# Morpheus_bottom.net
KiCad netlist of a schematic drawn in Altium Designer
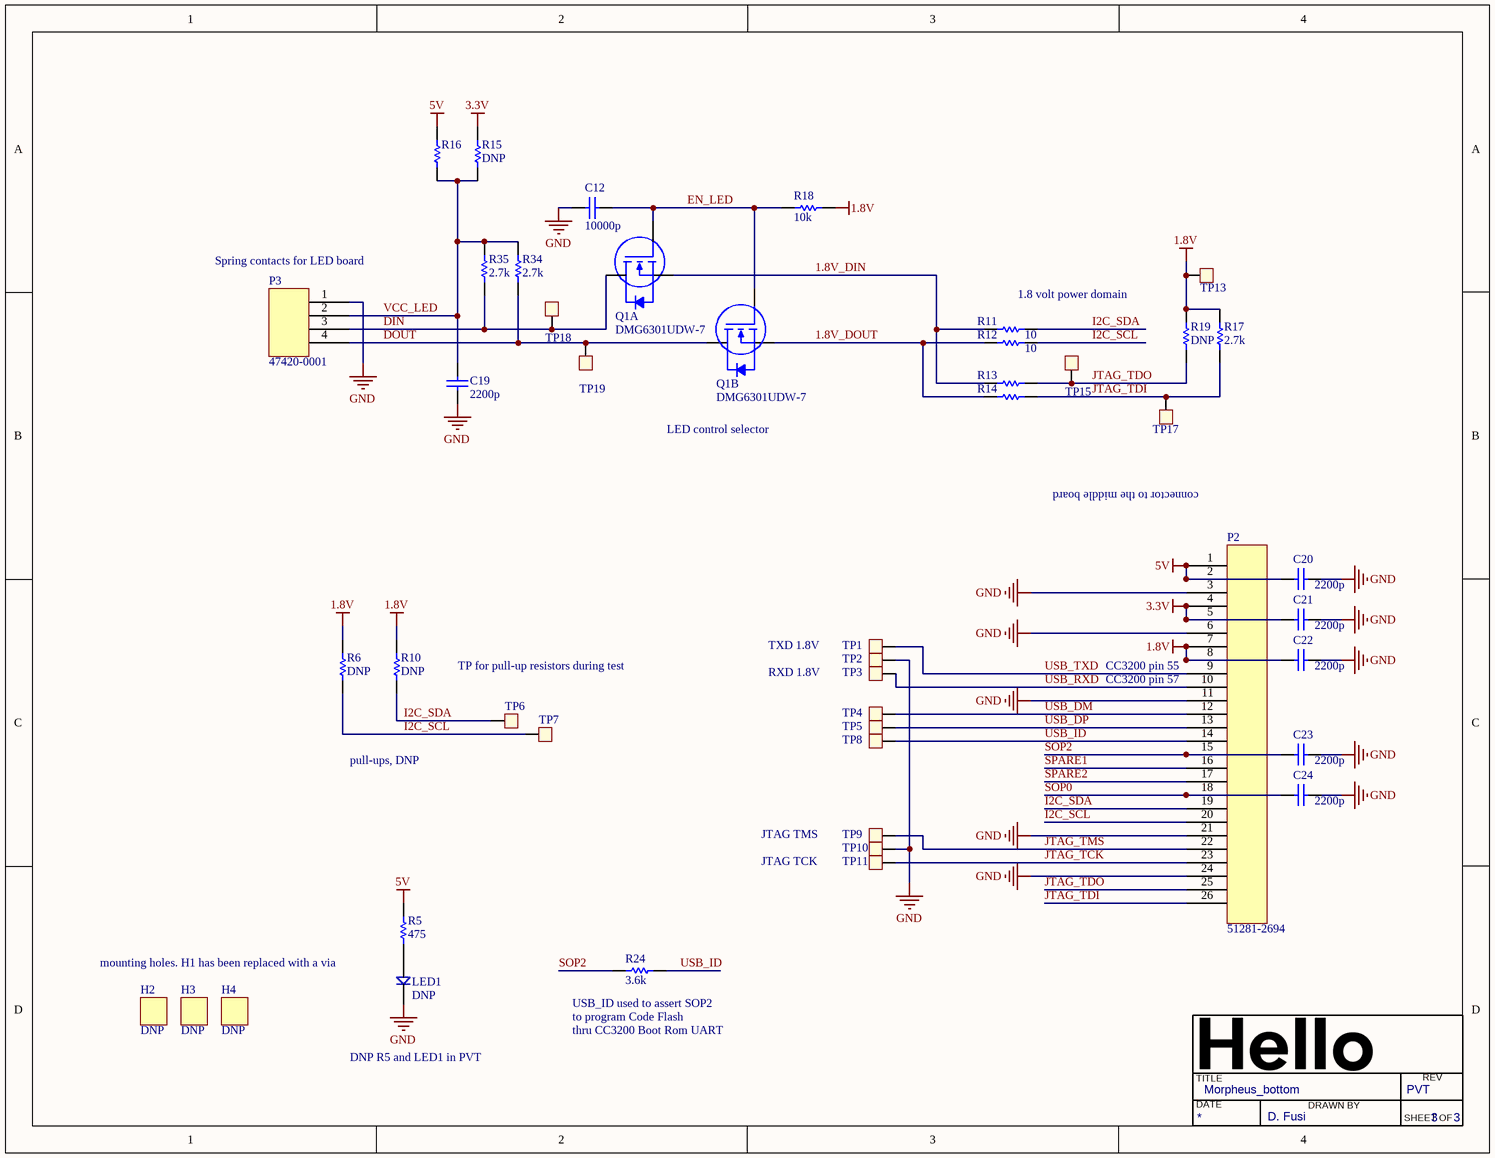
[diagram p0: Morpheus_bottom.SchDoc]

(export (version "E")
  (design (tool "Eeschema 10.0.6"))
  (components
    (comp (ref "C12")
      (value "10000p")
      (footprint "CAP0603_SENSE_DVT")
      (description "CAP CER 10000PF 50V 10% X7R 0603")
      (fields (field (name "TOLERANCE") "10%") (field (name "VOLTAGE") "50"))
      (libsource (lib "Morpheus_pill") (part "C_10000p_10_50_X7R_0603"))
    )
    (comp (ref "C19")
      (value "2200p")
      (footprint "CAP0402_SENSE_DVT")
      (description "CAP CER 2200PF 16V 10% X7R 0402")
      (fields (field (name "TOLERANCE") "10 %") (field (name "VOLTAGE") "16V"))
      (libsource (lib "Morpheus_pill") (part "C_2200p_5_16_STD_0402"))
    )
    (comp (ref "C20")
      (value "2200p")
      (footprint "CAP0402_SENSE_DVT")
      (description "CAP CER 2200PF 16V 10% X7R 0402")
      (fields (field (name "TOLERANCE") "10 %") (field (name "VOLTAGE") "16V"))
      (libsource (lib "Morpheus_pill") (part "C_2200p_5_16_STD_0402"))
    )
    (comp (ref "C21")
      (value "2200p")
      (footprint "CAP0402_SENSE_DVT")
      (description "CAP CER 2200PF 16V 10% X7R 0402")
      (fields (field (name "TOLERANCE") "10 %") (field (name "VOLTAGE") "16V"))
      (libsource (lib "Morpheus_pill") (part "C_2200p_5_16_STD_0402"))
    )
    (comp (ref "C22")
      (value "2200p")
      (footprint "CAP0402_SENSE_DVT")
      (description "CAP CER 2200PF 16V 10% X7R 0402")
      (fields (field (name "TOLERANCE") "10 %") (field (name "VOLTAGE") "16V"))
      (libsource (lib "Morpheus_pill") (part "C_2200p_5_16_STD_0402"))
    )
    (comp (ref "C23")
      (value "2200p")
      (footprint "CAP0402_SENSE_DVT")
      (description "CAP CER 2200PF 16V 10% X7R 0402")
      (fields (field (name "TOLERANCE") "10 %") (field (name "VOLTAGE") "16V"))
      (libsource (lib "Morpheus_pill") (part "C_2200p_5_16_STD_0402"))
    )
    (comp (ref "C24")
      (value "2200p")
      (footprint "CAP0402_SENSE_DVT")
      (description "CAP CER 2200PF 16V 10% X7R 0402")
      (fields (field (name "TOLERANCE") "10 %") (field (name "VOLTAGE") "16V"))
      (libsource (lib "Morpheus_pill") (part "C_2200p_5_16_STD_0402"))
    )
    (comp (ref "H2")
      (value "DNP")
      (footprint "HOLE_ROUND_1.8mm")
      (description "general purpose hole")
      (libsource (lib "Morpheus_pill") (part "Hole"))
    )
    (comp (ref "H3")
      (value "DNP")
      (footprint "HOLE_ROUND_1.8mm")
      (description "general purpose hole")
      (libsource (lib "Morpheus_pill") (part "Hole"))
    )
    (comp (ref "H4")
      (value "DNP")
      (footprint "HOLE_ROUND_1.8mm")
      (description "general purpose hole")
      (libsource (lib "Morpheus_pill") (part "Hole"))
    )
    (comp (ref "LED1")
      (value "DNP")
      (footprint "LED_Kingbright")
      (description "Kingbright Green SMT LED")
      (libsource (lib "Morpheus_pill") (part "APT2012SGC"))
    )
    (comp (ref "P2")
      (value "51281-2694")
      (footprint "molex_51281-2694_reverse")
      (description "Molex 26-pin 0.5mm pitch connector")
      (libsource (lib "Morpheus_pill") (part "51281-011"))
    )
    (comp (ref "P3")
      (value "47420-0001")
      (footprint "molex_47420-0001")
      (description "Molex 4-pin spring connector 1.8 mm working height")
      (libsource (lib "Morpheus_pill") (part "molex_47420-0001"))
    )
    (comp (ref "Q1")
      (value "DMG6301UDW-7")
      (footprint "SC-70-6")
      (description "MOSFET 2N-CH 25V 240MA SOT363")
      (libsource (lib "") (part "DMG6301UDW-7_1"))
    )
    (comp (ref "R5")
      (value "475")
      (footprint "RES0402_SENSE_DVT")
      (description "RES SMD 475 OHM 1% 1/16W 0402")
      (fields (field (name "TOLERANCE") "1 %") (field (name "POWER") "0.1 W"))
      (libsource (lib "Morpheus_pill") (part "R_475_1_0.1_0402"))
    )
    (comp (ref "R6")
      (value "DNP")
      (footprint "RES0603_SENSE_DVT")
      (description "Chip Resistor")
      (fields (field (name "TOLERANCE") "1 %") (field (name "POWER") "0.1 W"))
      (libsource (lib "Morpheus_pill") (part "R_2.7k_1_0.1_0603"))
    )
    (comp (ref "R10")
      (value "DNP")
      (footprint "RES0603_SENSE_DVT")
      (description "Chip Resistor")
      (fields (field (name "TOLERANCE") "1 %") (field (name "POWER") "0.1 W"))
      (libsource (lib "Morpheus_pill") (part "R_2.7k_1_0.1_0603"))
    )
    (comp (ref "R11")
      (value "10")
      (footprint "RES0402_SENSE_DVT")
      (description "RES SMD 10 OHM 1% 1/16W 0402")
      (fields (field (name "TOLERANCE") "1 %") (field (name "POWER") "1/16W"))
      (libsource (lib "Morpheus_pill") (part "R_10_1_0.1_0402"))
    )
    (comp (ref "R12")
      (value "10")
      (footprint "RES0402_SENSE_DVT")
      (description "RES SMD 10 OHM 1% 1/16W 0402")
      (fields (field (name "TOLERANCE") "1 %") (field (name "POWER") "1/16W"))
      (libsource (lib "Morpheus_pill") (part "R_10_1_0.1_0402"))
    )
    (comp (ref "R13")
      (value "R_0_jumper_0.1_0402")
      (footprint "RES0402-SENSE-DVT")
      (description "RES SMD 0.0 OHM JUMPER 1/16W")
      (fields (field (name "TOLERANCE") "Jumper") (field (name "POWER") "1/16W"))
      (libsource (lib "Morpheus_pill") (part "R_0_jumper_0.1_0402"))
    )
    (comp (ref "R14")
      (value "R_0_jumper_0.1_0402")
      (footprint "RES0402-SENSE-DVT")
      (description "RES SMD 0.0 OHM JUMPER 1/16W")
      (fields (field (name "TOLERANCE") "Jumper") (field (name "POWER") "1/16W"))
      (libsource (lib "Morpheus_pill") (part "R_0_jumper_0.1_0402"))
    )
    (comp (ref "R15")
      (value "DNP")
      (footprint "RES0603_SENSE_DVT")
      (description "Chip Resistor")
      (fields (field (name "TOLERANCE") "1 %") (field (name "POWER") "0.1 W"))
      (libsource (lib "Morpheus_pill") (part "R_2.7k_1_0.1_0603"))
    )
    (comp (ref "R16")
      (value "R_0_jumper_0.1_0402")
      (footprint "RES0402-SENSE-DVT")
      (description "RES SMD 0.0 OHM JUMPER 1/16W")
      (fields (field (name "TOLERANCE") "Jumper") (field (name "POWER") "1/16W"))
      (libsource (lib "Morpheus_pill") (part "R_0_jumper_0.1_0402"))
    )
    (comp (ref "R17")
      (value "2.7k")
      (footprint "RES0402_SENSE_DVT")
      (description "RES SMD 2.7K OHM 5% 1/16W 0402")
      (fields (field (name "TOLERANCE") "5 %") (field (name "POWER") "1/16W"))
      (libsource (lib "Morpheus_pill") (part "R_2.7k_5_0.1_0402"))
    )
    (comp (ref "R18")
      (value "10k")
      (footprint "RES0402_SENSE_DVT")
      (description "RES SMD 10K OHM 5% 1/16W 0402")
      (fields (field (name "TOLERANCE") "5 %") (field (name "POWER") "1/16W"))
      (libsource (lib "Morpheus_pill") (part "R_10k_5_0.1_0402"))
    )
    (comp (ref "R19")
      (value "DNP")
      (footprint "RES0402_SENSE_DVT")
      (description "RES SMD 2.7K OHM 5% 1/16W 0402")
      (fields (field (name "TOLERANCE") "5 %") (field (name "POWER") "1/16W"))
      (libsource (lib "Morpheus_pill") (part "R_2.7k_5_0.1_0402"))
    )
    (comp (ref "R24")
      (value "3.6k")
      (footprint "RES0402_SENSE_DVT")
      (description "RES SMD 3.6K OHM 1% 1/16W 0402")
      (fields (field (name "TOLERANCE") "1 %") (field (name "POWER") "1/16W"))
      (libsource (lib "Morpheus_pill") (part "R_3.6k_1_0.1_0402"))
    )
    (comp (ref "R34")
      (value "2.7k")
      (footprint "RES0402_SENSE_DVT")
      (description "RES SMD 2.7K OHM 5% 1/16W 0402")
      (fields (field (name "TOLERANCE") "5 %") (field (name "POWER") "1/16W"))
      (libsource (lib "Morpheus_pill") (part "R_2.7k_5_0.1_0402"))
    )
    (comp (ref "R35")
      (value "2.7k")
      (footprint "RES0402_SENSE_DVT")
      (description "RES SMD 2.7K OHM 5% 1/16W 0402")
      (fields (field (name "TOLERANCE") "5 %") (field (name "POWER") "1/16W"))
      (libsource (lib "Morpheus_pill") (part "R_2.7k_5_0.1_0402"))
    )
    (comp (ref "TP1")
      (value "TP")
      (footprint "TP-1.1")
      (description "testpoint")
      (libsource (lib "Morpheus_pill") (part "TP"))
    )
    (comp (ref "TP2")
      (value "TP")
      (footprint "TP-1.1")
      (description "testpoint")
      (libsource (lib "Morpheus_pill") (part "TP"))
    )
    (comp (ref "TP3")
      (value "TP")
      (footprint "TP-1.1")
      (description "testpoint")
      (libsource (lib "Morpheus_pill") (part "TP"))
    )
    (comp (ref "TP4")
      (value "TP")
      (footprint "TP-1.1")
      (description "testpoint")
      (libsource (lib "Morpheus_pill") (part "TP"))
    )
    (comp (ref "TP5")
      (value "TP")
      (footprint "TP-1.1")
      (description "testpoint")
      (libsource (lib "Morpheus_pill") (part "TP"))
    )
    (comp (ref "TP6")
      (value "TP")
      (footprint "TP-1.1")
      (description "testpoint")
      (libsource (lib "") (part "TP_2"))
    )
    (comp (ref "TP7")
      (value "TP")
      (footprint "TP-1.1")
      (description "testpoint")
      (libsource (lib "") (part "TP_2"))
    )
    (comp (ref "TP8")
      (value "TP")
      (footprint "TP-1.1")
      (description "testpoint")
      (libsource (lib "Morpheus_pill") (part "TP"))
    )
    (comp (ref "TP9")
      (value "TP")
      (footprint "TP-1.1")
      (description "testpoint")
      (libsource (lib "Morpheus_pill") (part "TP"))
    )
    (comp (ref "TP10")
      (value "TP")
      (footprint "TP-1.1")
      (description "testpoint")
      (libsource (lib "Morpheus_pill") (part "TP"))
    )
    (comp (ref "TP11")
      (value "TP")
      (footprint "TP-1.1")
      (description "testpoint")
      (libsource (lib "Morpheus_pill") (part "TP"))
    )
    (comp (ref "TP13")
      (value "TP")
      (footprint "TP-1.1")
      (description "testpoint")
      (libsource (lib "") (part "TP_2"))
    )
    (comp (ref "TP15")
      (value "TP")
      (footprint "TP-1.1")
      (description "testpoint")
      (libsource (lib "") (part "TP_3"))
    )
    (comp (ref "TP17")
      (value "TP")
      (footprint "TP-1.1")
      (description "testpoint")
      (libsource (lib "") (part "TP_1"))
    )
    (comp (ref "TP18")
      (value "TP")
      (footprint "TP-1.1")
      (description "testpoint")
      (libsource (lib "") (part "TP_3"))
    )
    (comp (ref "TP19")
      (value "TP")
      (footprint "TP-1.1")
      (description "testpoint")
      (libsource (lib "") (part "TP_1"))
    )
  )
  (nets
    (net (code "1") (name "/1.8V_DIN") (class "Default")
      (node (ref "Q1") (pin "1") (pinfunction "S1_1") (pintype "passive"))
      (node (ref "R11") (pin "2") (pinfunction "2_2") (pintype "passive"))
      (node (ref "R13") (pin "1") (pinfunction "1_1") (pintype "passive"))
    )
    (net (code "2") (name "/1.8V_DOUT") (class "Default")
      (node (ref "Q1") (pin "4") (pinfunction "S2_4") (pintype "passive"))
      (node (ref "R12") (pin "2") (pinfunction "2_2") (pintype "passive"))
      (node (ref "R14") (pin "1") (pinfunction "1_1") (pintype "passive"))
    )
    (net (code "3") (name "/DIN") (class "Default")
      (node (ref "P3") (pin "3") (pintype "passive"))
      (node (ref "Q1") (pin "6") (pinfunction "D1_6") (pintype "passive"))
      (node (ref "R35") (pin "1") (pinfunction "1_1") (pintype "passive"))
      (node (ref "TP18") (pin "1") (pinfunction "1_1") (pintype "passive"))
    )
    (net (code "4") (name "/DOUT") (class "Default")
      (node (ref "P3") (pin "4") (pintype "passive"))
      (node (ref "Q1") (pin "3") (pinfunction "D2_3") (pintype "passive"))
      (node (ref "R34") (pin "1") (pinfunction "1_1") (pintype "passive"))
      (node (ref "TP19") (pin "1") (pinfunction "1_1") (pintype "passive"))
    )
    (net (code "5") (name "/EN_LED") (class "Default")
      (node (ref "C12") (pin "1") (pinfunction "1_1") (pintype "passive"))
      (node (ref "Q1") (pin "2") (pinfunction "G1_2") (pintype "passive"))
      (node (ref "Q1") (pin "5") (pinfunction "G2_5") (pintype "passive"))
      (node (ref "R18") (pin "1") (pinfunction "1_1") (pintype "passive"))
    )
    (net (code "6") (name "/I2C_SCL") (class "Default")
      (node (ref "P2") (pin "20") (pintype "passive"))
      (node (ref "R12") (pin "1") (pinfunction "1_1") (pintype "passive"))
      (node (ref "R6") (pin "1") (pinfunction "1_1") (pintype "passive"))
      (node (ref "TP7") (pin "1") (pinfunction "1_1") (pintype "passive"))
    )
    (net (code "7") (name "/I2C_SDA") (class "Default")
      (node (ref "P2") (pin "19") (pintype "passive"))
      (node (ref "R10") (pin "1") (pinfunction "1_1") (pintype "passive"))
      (node (ref "R11") (pin "1") (pinfunction "1_1") (pintype "passive"))
      (node (ref "TP6") (pin "1") (pinfunction "1_1") (pintype "passive"))
    )
    (net (code "8") (name "/JTAG_TCK") (class "Default")
      (node (ref "P2") (pin "23") (pintype "passive"))
      (node (ref "TP11") (pin "1") (pinfunction "1_1") (pintype "passive"))
    )
    (net (code "9") (name "/JTAG_TDI") (class "Default")
      (node (ref "P2") (pin "26") (pintype "passive"))
      (node (ref "R14") (pin "2") (pinfunction "2_2") (pintype "passive"))
      (node (ref "R17") (pin "1") (pinfunction "1_1") (pintype "passive"))
      (node (ref "TP17") (pin "1") (pinfunction "1_1") (pintype "passive"))
    )
    (net (code "10") (name "/JTAG_TDO") (class "Default")
      (node (ref "P2") (pin "25") (pintype "passive"))
      (node (ref "R13") (pin "2") (pinfunction "2_2") (pintype "passive"))
      (node (ref "R19") (pin "1") (pinfunction "1_1") (pintype "passive"))
      (node (ref "TP15") (pin "1") (pinfunction "1_1") (pintype "passive"))
    )
    (net (code "11") (name "/JTAG_TMS") (class "Default")
      (node (ref "P2") (pin "22") (pintype "passive"))
      (node (ref "TP9") (pin "1") (pinfunction "1_1") (pintype "passive"))
    )
    (net (code "12") (name "/SOP0") (class "Default")
      (node (ref "C24") (pin "1") (pinfunction "1_1") (pintype "passive"))
      (node (ref "P2") (pin "18") (pintype "passive"))
    )
    (net (code "13") (name "/SOP2") (class "Default")
      (node (ref "C23") (pin "1") (pinfunction "1_1") (pintype "passive"))
      (node (ref "P2") (pin "15") (pintype "passive"))
      (node (ref "R24") (pin "1") (pinfunction "1_1") (pintype "passive"))
    )
    (net (code "14") (name "/SPARE1") (class "Default") (node (ref "P2") (pin "16") (pintype "passive")))
    (net (code "15") (name "/SPARE2") (class "Default") (node (ref "P2") (pin "17") (pintype "passive")))
    (net (code "16") (name "/USB_DM") (class "Default")
      (node (ref "P2") (pin "12") (pintype "passive"))
      (node (ref "TP4") (pin "1") (pinfunction "1_1") (pintype "passive"))
    )
    (net (code "17") (name "/USB_DP") (class "Default")
      (node (ref "P2") (pin "13") (pintype "passive"))
      (node (ref "TP5") (pin "1") (pinfunction "1_1") (pintype "passive"))
    )
    (net (code "18") (name "/USB_ID") (class "Default")
      (node (ref "P2") (pin "14") (pintype "passive"))
      (node (ref "R24") (pin "2") (pinfunction "2_2") (pintype "passive"))
      (node (ref "TP8") (pin "1") (pinfunction "1_1") (pintype "passive"))
    )
    (net (code "19") (name "/USB_RXD") (class "Default")
      (node (ref "P2") (pin "10") (pintype "passive"))
      (node (ref "TP3") (pin "1") (pinfunction "1_1") (pintype "passive"))
    )
    (net (code "20") (name "/USB_TXD") (class "Default")
      (node (ref "P2") (pin "9") (pintype "passive"))
      (node (ref "TP1") (pin "1") (pinfunction "1_1") (pintype "passive"))
    )
    (net (code "21") (name "/VCC_LED") (class "Default")
      (node (ref "C19") (pin "2") (pinfunction "2_2") (pintype "passive"))
      (node (ref "P3") (pin "2") (pintype "passive"))
      (node (ref "R15") (pin "1") (pinfunction "1_1") (pintype "passive"))
      (node (ref "R16") (pin "1") (pinfunction "1_1") (pintype "passive"))
      (node (ref "R34") (pin "2") (pinfunction "2_2") (pintype "passive"))
      (node (ref "R35") (pin "2") (pinfunction "2_2") (pintype "passive"))
    )
    (net (code "22") (name "1.8V") (class "Default")
      (node (ref "C22") (pin "1") (pinfunction "1_1") (pintype "passive"))
      (node (ref "P2") (pin "7") (pintype "passive"))
      (node (ref "P2") (pin "8") (pintype "passive"))
      (node (ref "R10") (pin "2") (pinfunction "2_2") (pintype "passive"))
      (node (ref "R17") (pin "2") (pinfunction "2_2") (pintype "passive"))
      (node (ref "R18") (pin "2") (pinfunction "2_2") (pintype "passive"))
      (node (ref "R19") (pin "2") (pinfunction "2_2") (pintype "passive"))
      (node (ref "R6") (pin "2") (pinfunction "2_2") (pintype "passive"))
      (node (ref "TP13") (pin "1") (pinfunction "1_1") (pintype "passive"))
    )
    (net (code "23") (name "3.3V") (class "Default")
      (node (ref "C21") (pin "1") (pinfunction "1_1") (pintype "passive"))
      (node (ref "P2") (pin "4") (pintype "passive"))
      (node (ref "P2") (pin "5") (pintype "passive"))
      (node (ref "R15") (pin "2") (pinfunction "2_2") (pintype "passive"))
    )
    (net (code "24") (name "5V") (class "Default")
      (node (ref "C20") (pin "1") (pinfunction "1_1") (pintype "passive"))
      (node (ref "P2") (pin "1") (pintype "passive"))
      (node (ref "P2") (pin "2") (pintype "passive"))
      (node (ref "R16") (pin "2") (pinfunction "2_2") (pintype "passive"))
      (node (ref "R5") (pin "2") (pinfunction "2_2") (pintype "passive"))
    )
    (net (code "25") (name "GND") (class "Default")
      (node (ref "C12") (pin "2") (pinfunction "2_2") (pintype "passive"))
      (node (ref "C19") (pin "1") (pinfunction "1_1") (pintype "passive"))
      (node (ref "C20") (pin "2") (pinfunction "2_2") (pintype "passive"))
      (node (ref "C21") (pin "2") (pinfunction "2_2") (pintype "passive"))
      (node (ref "C22") (pin "2") (pinfunction "2_2") (pintype "passive"))
      (node (ref "C23") (pin "2") (pinfunction "2_2") (pintype "passive"))
      (node (ref "C24") (pin "2") (pinfunction "2_2") (pintype "passive"))
      (node (ref "LED1") (pin "2") (pinfunction "Cathode_2") (pintype "passive"))
      (node (ref "P2") (pin "11") (pintype "passive"))
      (node (ref "P2") (pin "21") (pintype "passive"))
      (node (ref "P2") (pin "24") (pintype "passive"))
      (node (ref "P2") (pin "3") (pintype "passive"))
      (node (ref "P2") (pin "6") (pintype "passive"))
      (node (ref "P3") (pin "1") (pintype "passive"))
      (node (ref "TP10") (pin "1") (pinfunction "1_1") (pintype "passive"))
      (node (ref "TP2") (pin "1") (pinfunction "1_1") (pintype "passive"))
    )
    (net (code "26") (name "Net-(LED1-Anode)") (class "Default")
      (node (ref "LED1") (pin "1") (pinfunction "Anode_1") (pintype "passive"))
      (node (ref "R5") (pin "1") (pinfunction "1_1") (pintype "passive"))
    )
  )
)
